# GPS_IMU_SENSORS.net
KiCad netlist of a schematic drawn in Altium Designer
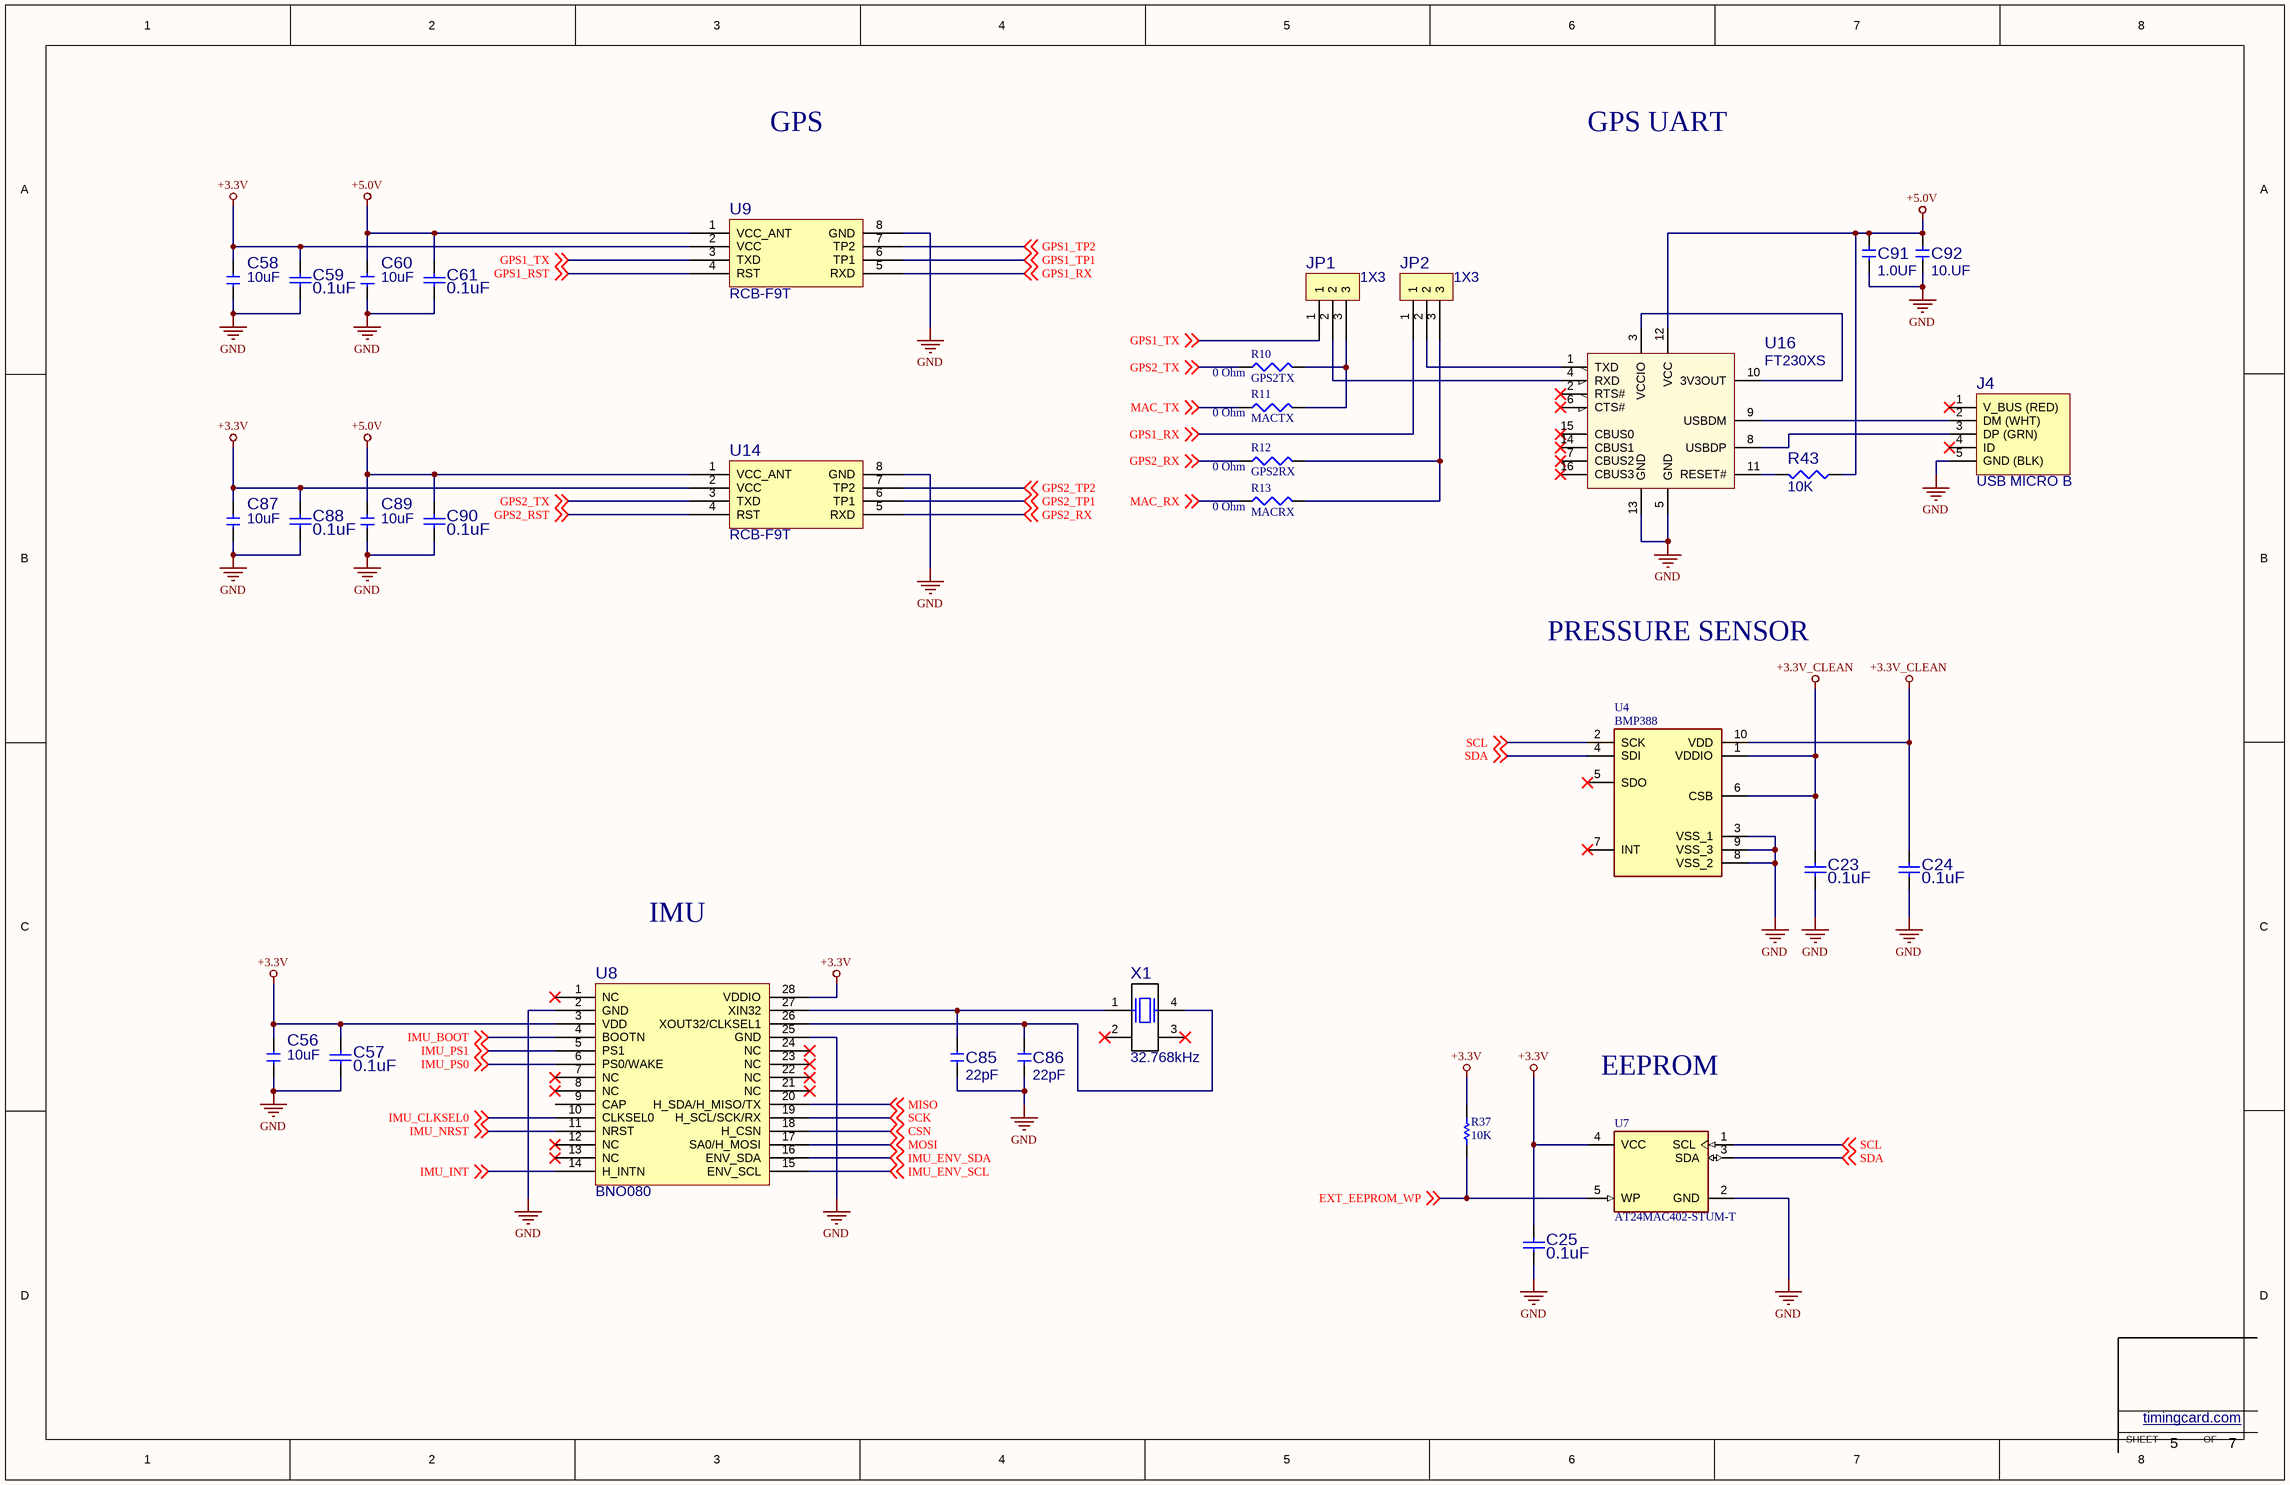
[diagram p0: GPS_IMU_SENSORS.SchDoc]

(export (version "E")
  (design (tool "Eeschema 10.0.6"))
  (components
    (comp (ref "C23")
      (value "0.1uF")
      (footprint "CAPC1608X87X45ML20T05")
      (description "C0603X104K5RACAUTO")
      (fields (field (name "MANUFACTURER") "Kemet"))
      (libsource (lib "Altium Content Vault") (part "CAP"))
    )
    (comp (ref "C24")
      (value "0.1uF")
      (footprint "CAPC1608X87X45ML20T05")
      (description "C0603X104K5RACAUTO")
      (fields (field (name "MANUFACTURER") "Kemet"))
      (libsource (lib "Altium Content Vault") (part "CAP"))
    )
    (comp (ref "C25")
      (value "0.1uF")
      (footprint "CAPC1608X87X45ML20T05")
      (description "C0603X104K5RACAUTO")
      (fields (field (name "MANUFACTURER") "Kemet"))
      (libsource (lib "Altium Content Vault") (part "CAP"))
    )
    (comp (ref "C56")
      (value "10uF")
      (footprint "CAPC2012X14N")
      (description "CAP, CER, 10.UF, 25V, 10%, X5R, 0805")
      (fields
        (field (name "MFG PART NUM") "TMK212BBJ106KG-T")
        (field (name "VALENTIUM PART NUM") "<VALENTIUM>")
      )
      (libsource (lib "Capacitors") (part "CAP_0805_10UF_25V"))
    )
    (comp (ref "C57")
      (value "0.1uF")
      (footprint "CAPC1608X87X45ML20T05")
      (description "C0603X104K5RACAUTO")
      (fields (field (name "MANUFACTURER") "Kemet"))
      (libsource (lib "Altium Content Vault") (part "CAP"))
    )
    (comp (ref "C58")
      (value "10uF")
      (footprint "CAPC2012X14N")
      (description "CAP, CER, 10.UF, 25V, 10%, X5R, 0805")
      (fields
        (field (name "MFG PART NUM") "TMK212BBJ106KG-T")
        (field (name "VALENTIUM PART NUM") "<VALENTIUM>")
      )
      (libsource (lib "Capacitors") (part "CAP_0805_10UF_25V"))
    )
    (comp (ref "C59")
      (value "0.1uF")
      (footprint "CAPC1608X87X45ML20T05")
      (description "C0603X104K5RACAUTO")
      (fields (field (name "MANUFACTURER") "Kemet"))
      (libsource (lib "Altium Content Vault") (part "CAP"))
    )
    (comp (ref "C60")
      (value "10uF")
      (footprint "CAPC2012X14N")
      (description "CAP, CER, 10.UF, 25V, 10%, X5R, 0805")
      (fields
        (field (name "MFG PART NUM") "TMK212BBJ106KG-T")
        (field (name "VALENTIUM PART NUM") "<VALENTIUM>")
      )
      (libsource (lib "Capacitors") (part "CAP_0805_10UF_25V"))
    )
    (comp (ref "C61")
      (value "0.1uF")
      (footprint "CAPC1608X87X45ML20T05")
      (description "C0603X104K5RACAUTO")
      (fields (field (name "MANUFACTURER") "Kemet"))
      (libsource (lib "Altium Content Vault") (part "CAP"))
    )
    (comp (ref "C85")
      (value "22pF")
      (footprint "CAPC1608X10N")
      (description "CAP, CER, 22.PF, 50V, 5%, NPO, 0603")
      (fields
        (field (name "MFG PART NUM") "C0603C220J5GACTU")
        (field (name "VALENTIUM PART NUM") "<VALENTIUM>")
      )
      (libsource (lib "Capacitors") (part "CAP_0603_22PF_50V"))
    )
    (comp (ref "C86")
      (value "22pF")
      (footprint "CAPC1608X10N")
      (description "CAP, CER, 22.PF, 50V, 5%, NPO, 0603")
      (fields
        (field (name "MFG PART NUM") "C0603C220J5GACTU")
        (field (name "VALENTIUM PART NUM") "<VALENTIUM>")
      )
      (libsource (lib "Capacitors") (part "CAP_0603_22PF_50V"))
    )
    (comp (ref "C87")
      (value "10uF")
      (footprint "CAPC2012X14N")
      (description "CAP, CER, 10.UF, 25V, 10%, X5R, 0805")
      (fields
        (field (name "MFG PART NUM") "TMK212BBJ106KG-T")
        (field (name "VALENTIUM PART NUM") "<VALENTIUM>")
      )
      (libsource (lib "Capacitors") (part "CAP_0805_10UF_25V"))
    )
    (comp (ref "C88")
      (value "0.1uF")
      (footprint "CAPC1608X87X45ML20T05")
      (description "C0603X104K5RACAUTO")
      (fields (field (name "MANUFACTURER") "Kemet"))
      (libsource (lib "Altium Content Vault") (part "CAP"))
    )
    (comp (ref "C89")
      (value "10uF")
      (footprint "CAPC2012X14N")
      (description "CAP, CER, 10.UF, 25V, 10%, X5R, 0805")
      (fields
        (field (name "MFG PART NUM") "TMK212BBJ106KG-T")
        (field (name "VALENTIUM PART NUM") "<VALENTIUM>")
      )
      (libsource (lib "Capacitors") (part "CAP_0805_10UF_25V"))
    )
    (comp (ref "C90")
      (value "0.1uF")
      (footprint "CAPC1608X87X45ML20T05")
      (description "C0603X104K5RACAUTO")
      (fields (field (name "MANUFACTURER") "Kemet"))
      (libsource (lib "Altium Content Vault") (part "CAP"))
    )
    (comp (ref "C91")
      (value "1.0UF")
      (footprint "CAPC2012X14N")
      (description "CAP, CER, 1.0UF, 25V, 10%, X5R, 0805")
      (fields
        (field (name "MFG PART NUM") "08053D105KAT2A")
        (field (name "VALENTIUM PART NUM") "<VALENTIUM>")
      )
      (libsource (lib "Capacitors") (part "CAP_0805_1UF_25V"))
    )
    (comp (ref "C92")
      (value "10.UF")
      (footprint "CAPC1608X10N")
      (description "CAP, CER, 10.UF, 25V, 20%, X5R, AEC-Q200, 0603")
      (fields
        (field (name "MFG PART NUM") "GRT188R61E106ME13D")
        (field (name "VALENTIUM PART NUM") "<VALENTIUM>")
      )
      (libsource (lib "Capacitors") (part "CAP_0603_10UF_25V"))
    )
    (comp (ref "J4")
      (value "USB MICRO B")
      (footprint "USB_47346-1001")
      (description "CONN, REC, USB, R/A, MICRO, TYPE B, 5 POS, SMT FLANGELESS")
      (fields (field (name "MFG PART NUM") "473461001") (field (name "VALENTIUM PART NUM") "<VALENTIUM>"))
      (libsource (lib "Connectors") (part "USB_B_473461001"))
    )
    (comp (ref "JP1")
      (value "1X3")
      (footprint "3PINV-100")
      (description "CONN, HDR, 1X3, VERT, .1, JUMPER, TH")
      (fields
        (field (name "MFG PART NUM") "TSW-103-08-G-S")
        (field (name "VALENTIUM PART NUM") "<VALENTIUM>")
      )
      (libsource (lib "Connectors") (part "JUMPER_3PIN"))
    )
    (comp (ref "JP2")
      (value "1X3")
      (footprint "3PINV-100")
      (description "CONN, HDR, 1X3, VERT, .1, JUMPER, TH")
      (fields
        (field (name "MFG PART NUM") "TSW-103-08-G-S")
        (field (name "VALENTIUM PART NUM") "<VALENTIUM>")
      )
      (libsource (lib "Connectors") (part "JUMPER_3PIN"))
    )
    (comp (ref "R10")
      (value "GPS2TX")
      (footprint "J1-0603")
      (description "Resistor")
      (fields (field (name "ALTIUM_VALUE") "0 Ohm") (field (name "PUBLISHER") "Altium Limited"))
      (libsource (lib "Miscellaneous Devices") (part "Res3"))
    )
    (comp (ref "R11")
      (value "MACTX")
      (footprint "J1-0603")
      (description "Resistor")
      (fields (field (name "ALTIUM_VALUE") "0 Ohm") (field (name "PUBLISHER") "Altium Limited"))
      (libsource (lib "Miscellaneous Devices") (part "Res3"))
    )
    (comp (ref "R12")
      (value "GPS2RX")
      (footprint "J1-0603")
      (description "Resistor")
      (fields (field (name "ALTIUM_VALUE") "0 Ohm") (field (name "PUBLISHER") "Altium Limited"))
      (libsource (lib "Miscellaneous Devices") (part "Res3"))
    )
    (comp (ref "R13")
      (value "MACRX")
      (footprint "J1-0603")
      (description "Resistor")
      (fields (field (name "ALTIUM_VALUE") "0 Ohm") (field (name "PUBLISHER") "Altium Limited"))
      (libsource (lib "Miscellaneous Devices") (part "Res3"))
    )
    (comp (ref "R37")
      (value "10K")
      (footprint "RESC1608X55X30LL15T20")
      (fields (field (name "TOLERANCE") "±1%") (field (name "MANUFACTURER") "Stackpole-Electronics-Inc."))
      (libsource (lib "Altium Content Vault") (part "RES-2"))
    )
    (comp (ref "R43")
      (value "10K")
      (footprint "RESC1608X50N")
      (description "RES, 10K, 1%, 1/10W, TF, 0603")
      (fields (field (name "MFG PART NUM") "ERJ-3EKF1002V") (field (name "VELENTIUM PART NUM") "<VELENTIUM>"))
      (libsource (lib "Resistors") (part "RES_0603_10K"))
    )
    (comp (ref "U4")
      (value "BMP388")
      (footprint "SamacSys:BMP388")
      (description "Integrated Circuit")
      (fields (field (name "MOUSER PART NUMBER") "262-BMP388"))
      (libsource (lib "*") (part "BMP388"))
    )
    (comp (ref "U7")
      (value "AT24MAC402-STUM-T")
      (footprint "FP-5TS1-IPC_C")
      (description "IC EEPROM 2K I2C 1MHZ SOT23-5")
      (fields
        (field (name "MANUFACTURER") "Microchip")
        (field (name "OCTOPART") "https://octopart.com/at24mac402-stum-t-microchip-77758112")
      )
      (libsource (lib "Altium Content Vault") (part "93fe34f5f049140596bab6421a6454b"))
    )
    (comp (ref "U8")
      (value "BNO080")
      (footprint "LGA-28")
      (description "MOD, IMU, 5.2X3.8, SMT")
      (fields (field (name "VELENTIUM PART NUM") "<V PART NUM>"))
      (libsource (lib "Modules") (part "BNO080"))
    )
    (comp (ref "U9")
      (value "RCB-F9T")
      (footprint "RCB-F9T")
      (description "MOD, GPS")
      (fields (field (name "VELENTIUM PART NUM") "<V PART NUM>"))
      (libsource (lib "Modules") (part "RCB-F9T"))
    )
    (comp (ref "U14")
      (value "RCB-F9T")
      (footprint "RCB-F9T")
      (description "MOD, GPS")
      (fields (field (name "VELENTIUM PART NUM") "<V PART NUM>"))
      (libsource (lib "Modules") (part "RCB-F9T"))
    )
    (comp (ref "U16")
      (value "FT230XS")
      (footprint "SOP64P600X170-16N")
      (description "IC, TCVR, FT230, USB TO UART, 5V, FTDI, 16SSOP")
      (fields (field (name "MFG PART NUM") "FT230XS-R") (field (name "VELENTIUM PART NUM") "<V PART NUM>"))
      (libsource (lib "IntegratedCircuits") (part "FT230XS-R"))
    )
    (comp (ref "X1")
      (value "32.768kHz")
      (footprint "SM8")
      (description "XTAL, 32.768KHZ, 6PF LOAD CAP, SMD, ROHS")
      (fields
        (field (name "MFG PART NUM") "MC-306 32.768K-E3:ROHS")
        (field (name "VALENTIUM PART NUM") "<VALENTIUM>")
      )
      (libsource (lib "Miscellaneous") (part "MC306"))
    )
  )
  (nets
    (net (code "1") (name "+3.3V") (class "Default")
      (node (ref "C25") (pin "2") (pinfunction "2_2") (pintype "passive"))
      (node (ref "C56") (pin "1") (pinfunction "1_1") (pintype "passive"))
      (node (ref "C57") (pin "2") (pinfunction "2_2") (pintype "passive"))
      (node (ref "C58") (pin "1") (pinfunction "1_1") (pintype "passive"))
      (node (ref "C59") (pin "2") (pinfunction "2_2") (pintype "passive"))
      (node (ref "C87") (pin "1") (pinfunction "1_1") (pintype "passive"))
      (node (ref "C88") (pin "2") (pinfunction "2_2") (pintype "passive"))
      (node (ref "R37") (pin "2") (pinfunction "2_2") (pintype "passive"))
      (node (ref "U14") (pin "2") (pinfunction "VCC_2") (pintype "passive"))
      (node (ref "U7") (pin "4") (pinfunction "VCC_4") (pintype "power_in"))
      (node (ref "U8") (pin "28") (pinfunction "VDDIO_28") (pintype "passive"))
      (node (ref "U8") (pin "3") (pinfunction "VDD_3") (pintype "passive"))
      (node (ref "U9") (pin "2") (pinfunction "VCC_2") (pintype "passive"))
    )
    (net (code "2") (name "+3.3V_CLEAN") (class "Default")
      (node (ref "C23") (pin "2") (pinfunction "2_2") (pintype "passive"))
      (node (ref "C24") (pin "2") (pinfunction "2_2") (pintype "passive"))
      (node (ref "U4") (pin "1") (pinfunction "VDDIO_1") (pintype "passive"))
      (node (ref "U4") (pin "10") (pinfunction "VDD_10") (pintype "passive"))
      (node (ref "U4") (pin "6") (pinfunction "CSB_6") (pintype "passive"))
    )
    (net (code "3") (name "+5.0V") (class "Default")
      (node (ref "C60") (pin "1") (pinfunction "1_1") (pintype "passive"))
      (node (ref "C61") (pin "2") (pinfunction "2_2") (pintype "passive"))
      (node (ref "C89") (pin "1") (pinfunction "1_1") (pintype "passive"))
      (node (ref "C90") (pin "2") (pinfunction "2_2") (pintype "passive"))
      (node (ref "C91") (pin "2") (pinfunction "2_2") (pintype "passive"))
      (node (ref "C92") (pin "2") (pinfunction "2_2") (pintype "passive"))
      (node (ref "R43") (pin "1") (pinfunction "1_1") (pintype "passive"))
      (node (ref "U14") (pin "1") (pinfunction "VCC_ANT_1") (pintype "passive"))
      (node (ref "U16") (pin "12") (pinfunction "VCC_12") (pintype "passive"))
      (node (ref "U9") (pin "1") (pinfunction "VCC_ANT_1") (pintype "passive"))
    )
    (net (code "4") (name "CSN") (class "Default")
      (node (ref "U8") (pin "18") (pinfunction "H_CSN_18") (pintype "passive"))
    )
    (net (code "5") (name "EXT_EEPROM_WP") (class "Default")
      (node (ref "R37") (pin "1") (pinfunction "1_1") (pintype "passive"))
      (node (ref "U7") (pin "5") (pinfunction "WP_5") (pintype "input"))
    )
    (net (code "6") (name "GND") (class "Default")
      (node (ref "C23") (pin "1") (pinfunction "1_1") (pintype "passive"))
      (node (ref "C24") (pin "1") (pinfunction "1_1") (pintype "passive"))
      (node (ref "C25") (pin "1") (pinfunction "1_1") (pintype "passive"))
      (node (ref "C56") (pin "2") (pinfunction "2_2") (pintype "passive"))
      (node (ref "C57") (pin "1") (pinfunction "1_1") (pintype "passive"))
      (node (ref "C58") (pin "2") (pinfunction "2_2") (pintype "passive"))
      (node (ref "C59") (pin "1") (pinfunction "1_1") (pintype "passive"))
      (node (ref "C60") (pin "2") (pinfunction "2_2") (pintype "passive"))
      (node (ref "C61") (pin "1") (pinfunction "1_1") (pintype "passive"))
      (node (ref "C85") (pin "1") (pinfunction "1_1") (pintype "passive"))
      (node (ref "C86") (pin "1") (pinfunction "1_1") (pintype "passive"))
      (node (ref "C87") (pin "2") (pinfunction "2_2") (pintype "passive"))
      (node (ref "C88") (pin "1") (pinfunction "1_1") (pintype "passive"))
      (node (ref "C89") (pin "2") (pinfunction "2_2") (pintype "passive"))
      (node (ref "C90") (pin "1") (pinfunction "1_1") (pintype "passive"))
      (node (ref "C91") (pin "1") (pinfunction "1_1") (pintype "passive"))
      (node (ref "C92") (pin "1") (pinfunction "1_1") (pintype "passive"))
      (node (ref "J4") (pin "5") (pinfunction "GND_(BLK)_5") (pintype "passive"))
      (node (ref "U14") (pin "8") (pinfunction "GND_8") (pintype "passive"))
      (node (ref "U16") (pin "13") (pinfunction "GND_13") (pintype "passive"))
      (node (ref "U16") (pin "5") (pinfunction "GND_5") (pintype "passive"))
      (node (ref "U4") (pin "3") (pinfunction "VSS_1_3") (pintype "passive"))
      (node (ref "U4") (pin "8") (pinfunction "VSS_2_8") (pintype "passive"))
      (node (ref "U4") (pin "9") (pinfunction "VSS_3_9") (pintype "passive"))
      (node (ref "U7") (pin "2") (pinfunction "GND_2") (pintype "power_in"))
      (node (ref "U8") (pin "2") (pinfunction "GND_2") (pintype "passive"))
      (node (ref "U8") (pin "25") (pinfunction "GND_25") (pintype "passive"))
      (node (ref "U9") (pin "8") (pinfunction "GND_8") (pintype "passive"))
    )
    (net (code "7") (name "GPS1_RST") (class "Default")
      (node (ref "U9") (pin "4") (pinfunction "RST_4") (pintype "passive"))
    )
    (net (code "8") (name "GPS1_RX") (class "Default")
      (node (ref "JP2") (pin "1") (pinfunction "1_1") (pintype "passive"))
      (node (ref "U9") (pin "5") (pinfunction "RXD_5") (pintype "passive"))
    )
    (net (code "9") (name "GPS1_TP1") (class "Default")
      (node (ref "U9") (pin "6") (pinfunction "TP1_6") (pintype "passive"))
    )
    (net (code "10") (name "GPS1_TP2") (class "Default")
      (node (ref "U9") (pin "7") (pinfunction "TP2_7") (pintype "passive"))
    )
    (net (code "11") (name "GPS1_TX") (class "Default")
      (node (ref "JP1") (pin "1") (pinfunction "1_1") (pintype "passive"))
      (node (ref "U9") (pin "3") (pinfunction "TXD_3") (pintype "passive"))
    )
    (net (code "12") (name "GPS2_RST") (class "Default")
      (node (ref "U14") (pin "4") (pinfunction "RST_4") (pintype "passive"))
    )
    (net (code "13") (name "GPS2_RX") (class "Default")
      (node (ref "R12") (pin "1") (pinfunction "1_1") (pintype "passive"))
      (node (ref "U14") (pin "5") (pinfunction "RXD_5") (pintype "passive"))
    )
    (net (code "14") (name "GPS2_TP1") (class "Default")
      (node (ref "U14") (pin "6") (pinfunction "TP1_6") (pintype "passive"))
    )
    (net (code "15") (name "GPS2_TP2") (class "Default")
      (node (ref "U14") (pin "7") (pinfunction "TP2_7") (pintype "passive"))
    )
    (net (code "16") (name "GPS2_TX") (class "Default")
      (node (ref "R10") (pin "1") (pinfunction "1_1") (pintype "passive"))
      (node (ref "U14") (pin "3") (pinfunction "TXD_3") (pintype "passive"))
    )
    (net (code "17") (name "IMU_BOOT") (class "Default")
      (node (ref "U8") (pin "4") (pinfunction "BOOTN_4") (pintype "passive"))
    )
    (net (code "18") (name "IMU_CLKSEL0") (class "Default")
      (node (ref "U8") (pin "10") (pinfunction "CLKSEL0_10") (pintype "passive"))
    )
    (net (code "19") (name "IMU_ENV_SCL") (class "Default")
      (node (ref "U8") (pin "15") (pinfunction "ENV_SCL_15") (pintype "passive"))
    )
    (net (code "20") (name "IMU_ENV_SDA") (class "Default")
      (node (ref "U8") (pin "16") (pinfunction "ENV_SDA_16") (pintype "passive"))
    )
    (net (code "21") (name "IMU_INT") (class "Default")
      (node (ref "U8") (pin "14") (pinfunction "H_INTN_14") (pintype "passive"))
    )
    (net (code "22") (name "IMU_NRST") (class "Default")
      (node (ref "U8") (pin "11") (pinfunction "NRST_11") (pintype "passive"))
    )
    (net (code "23") (name "IMU_PS0") (class "Default")
      (node (ref "U8") (pin "6") (pinfunction "PS0/WAKE_6") (pintype "passive"))
    )
    (net (code "24") (name "IMU_PS1") (class "Default")
      (node (ref "U8") (pin "5") (pinfunction "PS1_5") (pintype "passive"))
    )
    (net (code "25") (name "MAC_RX") (class "Default")
      (node (ref "R13") (pin "1") (pinfunction "1_1") (pintype "passive"))
    )
    (net (code "26") (name "MAC_TX") (class "Default")
      (node (ref "R11") (pin "1") (pinfunction "1_1") (pintype "passive"))
    )
    (net (code "27") (name "MISO") (class "Default")
      (node (ref "U8") (pin "20") (pinfunction "H_SDA/H_MISO/TX_20") (pintype "passive"))
    )
    (net (code "28") (name "MOSI") (class "Default")
      (node (ref "U8") (pin "17") (pinfunction "SA0/H_MOSI_17") (pintype "passive"))
    )
    (net (code "29") (name "Net-(J4-DM_(WHT))") (class "Default")
      (node (ref "J4") (pin "2") (pinfunction "DM_(WHT)_2") (pintype "passive"))
      (node (ref "U16") (pin "9") (pinfunction "USBDM_9") (pintype "passive"))
    )
    (net (code "30") (name "Net-(J4-DP_(GRN))") (class "Default")
      (node (ref "J4") (pin "3") (pinfunction "DP_(GRN)_3") (pintype "passive"))
      (node (ref "U16") (pin "8") (pinfunction "USBDP_8") (pintype "passive"))
    )
    (net (code "31") (name "Net-(JP1-Pad3)") (class "Default")
      (node (ref "JP1") (pin "3") (pinfunction "3_3") (pintype "passive"))
      (node (ref "R10") (pin "2") (pinfunction "2_2") (pintype "passive"))
      (node (ref "R11") (pin "2") (pinfunction "2_2") (pintype "passive"))
    )
    (net (code "32") (name "Net-(JP2-Pad3)") (class "Default")
      (node (ref "JP2") (pin "3") (pinfunction "3_3") (pintype "passive"))
      (node (ref "R12") (pin "2") (pinfunction "2_2") (pintype "passive"))
      (node (ref "R13") (pin "2") (pinfunction "2_2") (pintype "passive"))
    )
    (net (code "33") (name "Net-(U8-XIN32)") (class "Default")
      (node (ref "C85") (pin "2") (pinfunction "2_2") (pintype "passive"))
      (node (ref "U8") (pin "27") (pinfunction "XIN32_27") (pintype "passive"))
      (node (ref "X1") (pin "1") (pinfunction "1_1") (pintype "passive"))
    )
    (net (code "34") (name "Net-(U8-XOUT32{slash}CLKSEL1)") (class "Default")
      (node (ref "C86") (pin "2") (pinfunction "2_2") (pintype "passive"))
      (node (ref "U8") (pin "26") (pinfunction "XOUT32/CLKSEL1_26") (pintype "passive"))
      (node (ref "X1") (pin "4") (pinfunction "4_4") (pintype "passive"))
    )
    (net (code "35") (name "Net-(U16-3V3OUT)") (class "Default")
      (node (ref "U16") (pin "10") (pinfunction "3V3OUT_10") (pintype "passive"))
      (node (ref "U16") (pin "3") (pinfunction "VCCIO_3") (pintype "passive"))
    )
    (net (code "36") (name "Net-(U16-RESET#)") (class "Default")
      (node (ref "R43") (pin "2") (pinfunction "2_2") (pintype "passive"))
      (node (ref "U16") (pin "11") (pinfunction "RESET#_11") (pintype "passive"))
    )
    (net (code "37") (name "Net-(U16-RXD)") (class "Default")
      (node (ref "JP1") (pin "2") (pinfunction "2_2") (pintype "passive"))
      (node (ref "U16") (pin "4") (pinfunction "RXD_4") (pintype "passive"))
    )
    (net (code "38") (name "Net-(U16-TXD)") (class "Default")
      (node (ref "JP2") (pin "2") (pinfunction "2_2") (pintype "passive"))
      (node (ref "U16") (pin "1") (pinfunction "TXD_1") (pintype "passive"))
    )
    (net (code "39") (name "SCK") (class "Default")
      (node (ref "U8") (pin "19") (pinfunction "H_SCL/SCK/RX_19") (pintype "passive"))
    )
    (net (code "40") (name "SCL") (class "Default")
      (node (ref "U4") (pin "2") (pinfunction "SCK_2") (pintype "passive"))
      (node (ref "U7") (pin "1") (pinfunction "SCL_1") (pintype "input"))
    )
    (net (code "41") (name "SDA") (class "Default")
      (node (ref "U4") (pin "4") (pinfunction "SDI_4") (pintype "passive"))
      (node (ref "U7") (pin "3") (pinfunction "SDA_3") (pintype "bidirectional"))
    )
    (net (code "42") (name "unconnected-(J4-ID-Pad4)") (class "Default")
      (node (ref "J4") (pin "4") (pinfunction "ID_4") (pintype "passive+no_connect"))
    )
    (net (code "43") (name "unconnected-(J4-V_BUS_(RED)-Pad1)") (class "Default")
      (node (ref "J4") (pin "1") (pinfunction "V_BUS_(RED)_1") (pintype "passive+no_connect"))
    )
    (net (code "44") (name "unconnected-(U4-INT-Pad7)") (class "Default")
      (node (ref "U4") (pin "7") (pinfunction "INT_7") (pintype "passive+no_connect"))
    )
    (net (code "45") (name "unconnected-(U4-SDO-Pad5)") (class "Default")
      (node (ref "U4") (pin "5") (pinfunction "SDO_5") (pintype "passive+no_connect"))
    )
    (net (code "46") (name "unconnected-(U8-CAP-Pad9)") (class "Default")
      (node (ref "U8") (pin "9") (pinfunction "CAP_9") (pintype "passive"))
    )
    (net (code "47") (name "unconnected-(U8-NC-Pad1)") (class "Default")
      (node (ref "U8") (pin "1") (pinfunction "NC_1") (pintype "passive+no_connect"))
    )
    (net (code "48") (name "unconnected-(U8-NC-Pad7)") (class "Default")
      (node (ref "U8") (pin "7") (pinfunction "NC_7") (pintype "passive+no_connect"))
    )
    (net (code "49") (name "unconnected-(U8-NC-Pad8)") (class "Default")
      (node (ref "U8") (pin "8") (pinfunction "NC_8") (pintype "passive+no_connect"))
    )
    (net (code "50") (name "unconnected-(U8-NC-Pad12)") (class "Default")
      (node (ref "U8") (pin "12") (pinfunction "NC_12") (pintype "passive+no_connect"))
    )
    (net (code "51") (name "unconnected-(U8-NC-Pad13)") (class "Default")
      (node (ref "U8") (pin "13") (pinfunction "NC_13") (pintype "passive+no_connect"))
    )
    (net (code "52") (name "unconnected-(U8-NC-Pad21)") (class "Default")
      (node (ref "U8") (pin "21") (pinfunction "NC_21") (pintype "passive+no_connect"))
    )
    (net (code "53") (name "unconnected-(U8-NC-Pad22)") (class "Default")
      (node (ref "U8") (pin "22") (pinfunction "NC_22") (pintype "passive+no_connect"))
    )
    (net (code "54") (name "unconnected-(U8-NC-Pad23)") (class "Default")
      (node (ref "U8") (pin "23") (pinfunction "NC_23") (pintype "passive+no_connect"))
    )
    (net (code "55") (name "unconnected-(U8-NC-Pad24)") (class "Default")
      (node (ref "U8") (pin "24") (pinfunction "NC_24") (pintype "passive+no_connect"))
    )
    (net (code "56") (name "unconnected-(U16-CBUS0-Pad15)") (class "Default")
      (node (ref "U16") (pin "15") (pinfunction "CBUS0_15") (pintype "passive+no_connect"))
    )
    (net (code "57") (name "unconnected-(U16-CBUS1-Pad14)") (class "Default")
      (node (ref "U16") (pin "14") (pinfunction "CBUS1_14") (pintype "passive+no_connect"))
    )
    (net (code "58") (name "unconnected-(U16-CBUS2-Pad7)") (class "Default")
      (node (ref "U16") (pin "7") (pinfunction "CBUS2_7") (pintype "passive+no_connect"))
    )
    (net (code "59") (name "unconnected-(U16-CBUS3-Pad16)") (class "Default")
      (node (ref "U16") (pin "16") (pinfunction "CBUS3_16") (pintype "passive+no_connect"))
    )
    (net (code "60") (name "unconnected-(U16-CTS#-Pad6)") (class "Default")
      (node (ref "U16") (pin "6") (pinfunction "CTS#_6") (pintype "passive+no_connect"))
    )
    (net (code "61") (name "unconnected-(U16-RTS#-Pad2)") (class "Default")
      (node (ref "U16") (pin "2") (pinfunction "RTS#_2") (pintype "passive+no_connect"))
    )
    (net (code "62") (name "unconnected-(X1-Pad2)") (class "Default")
      (node (ref "X1") (pin "2") (pinfunction "2_2") (pintype "passive+no_connect"))
    )
    (net (code "63") (name "unconnected-(X1-Pad3)") (class "Default")
      (node (ref "X1") (pin "3") (pinfunction "3_3") (pintype "passive+no_connect"))
    )
  )
)
